# MineralFire-0_3-smd-inprogress.net
KiCad netlist of a schematic drawn in EAGLE
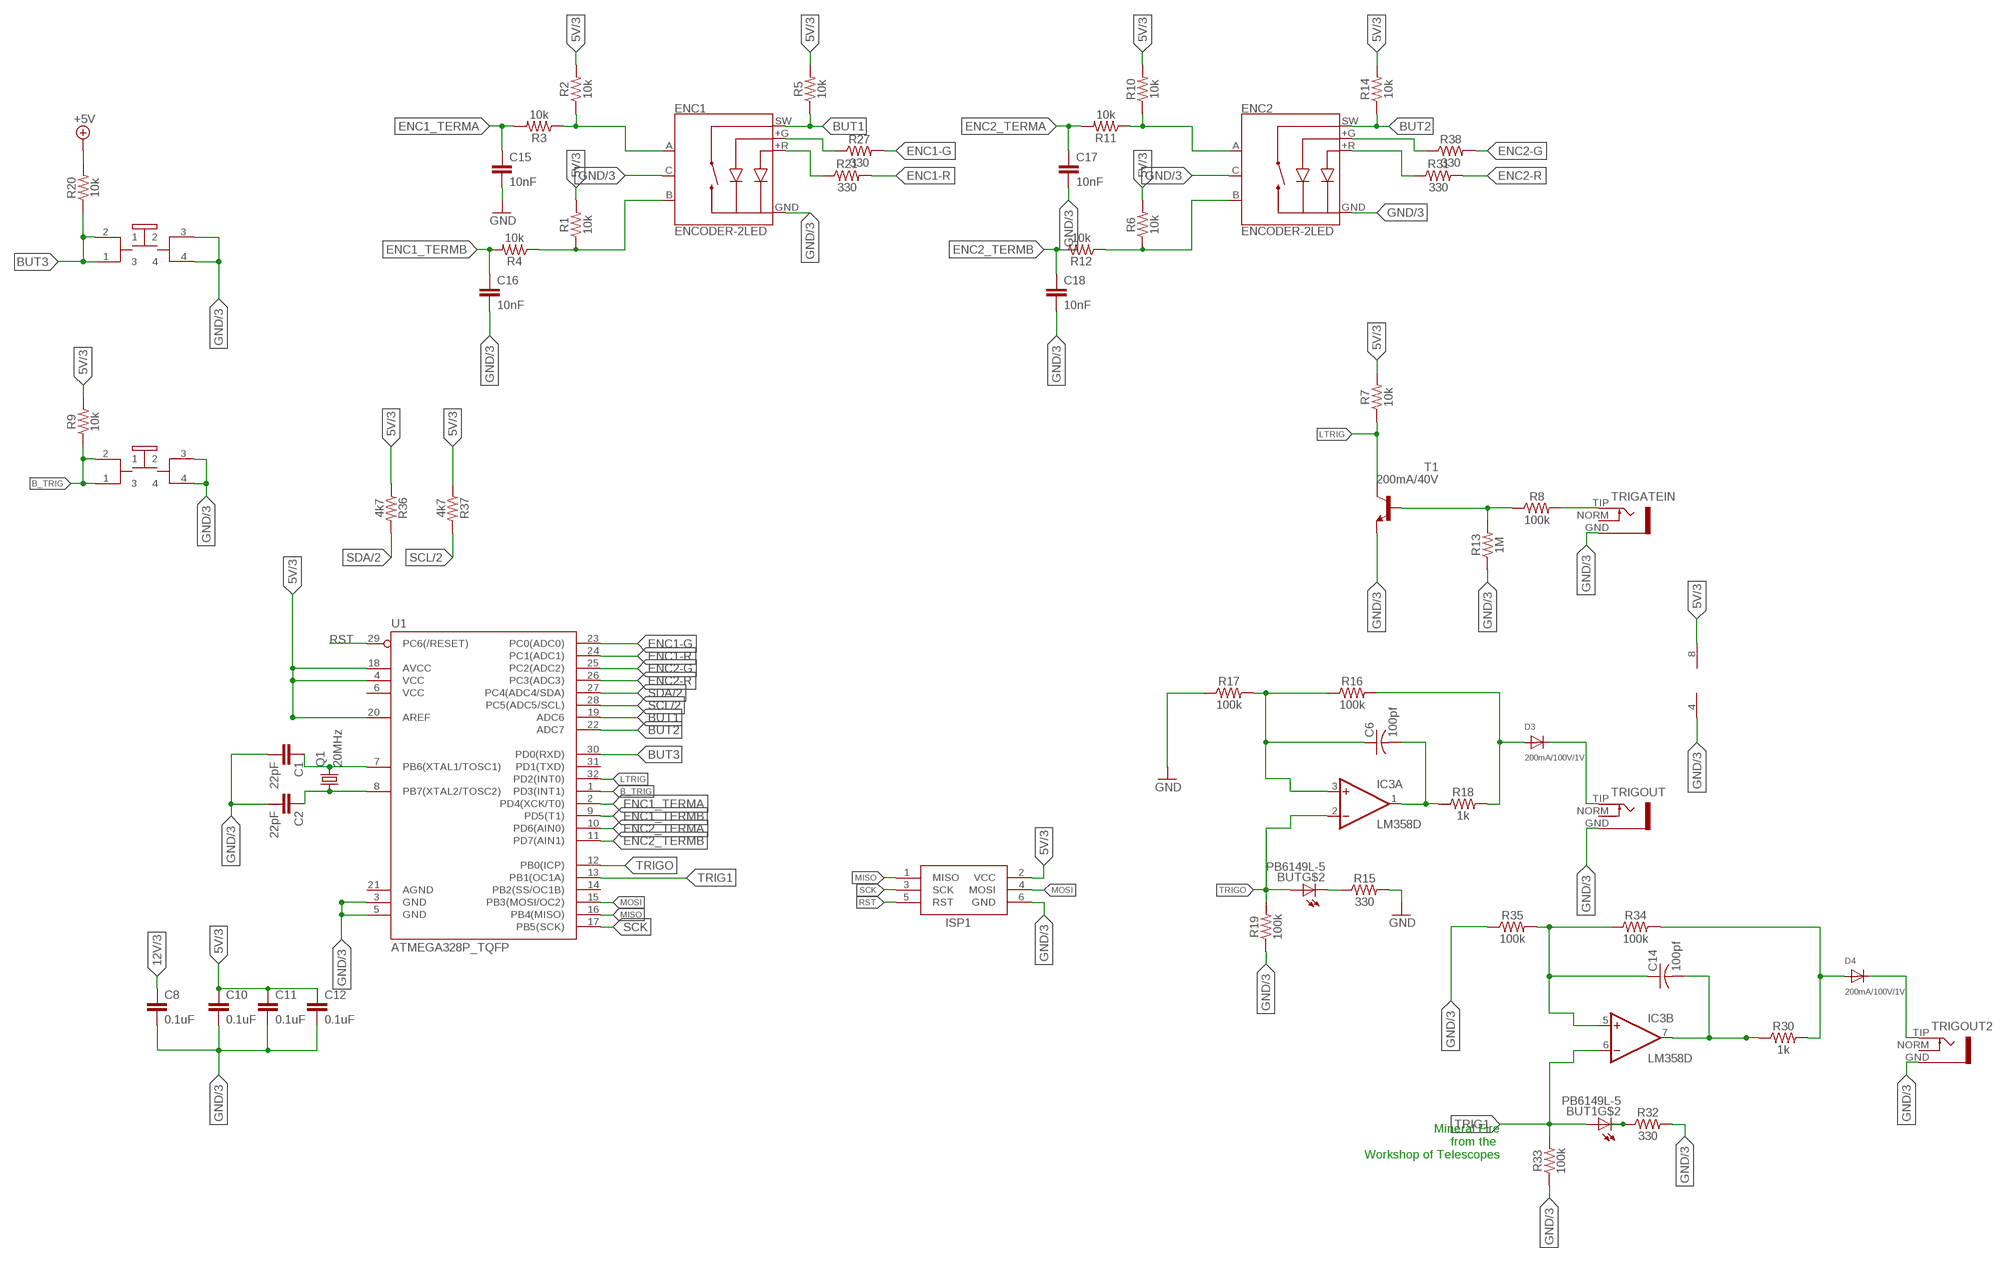
[diagram p0: schematic, sheet 1]
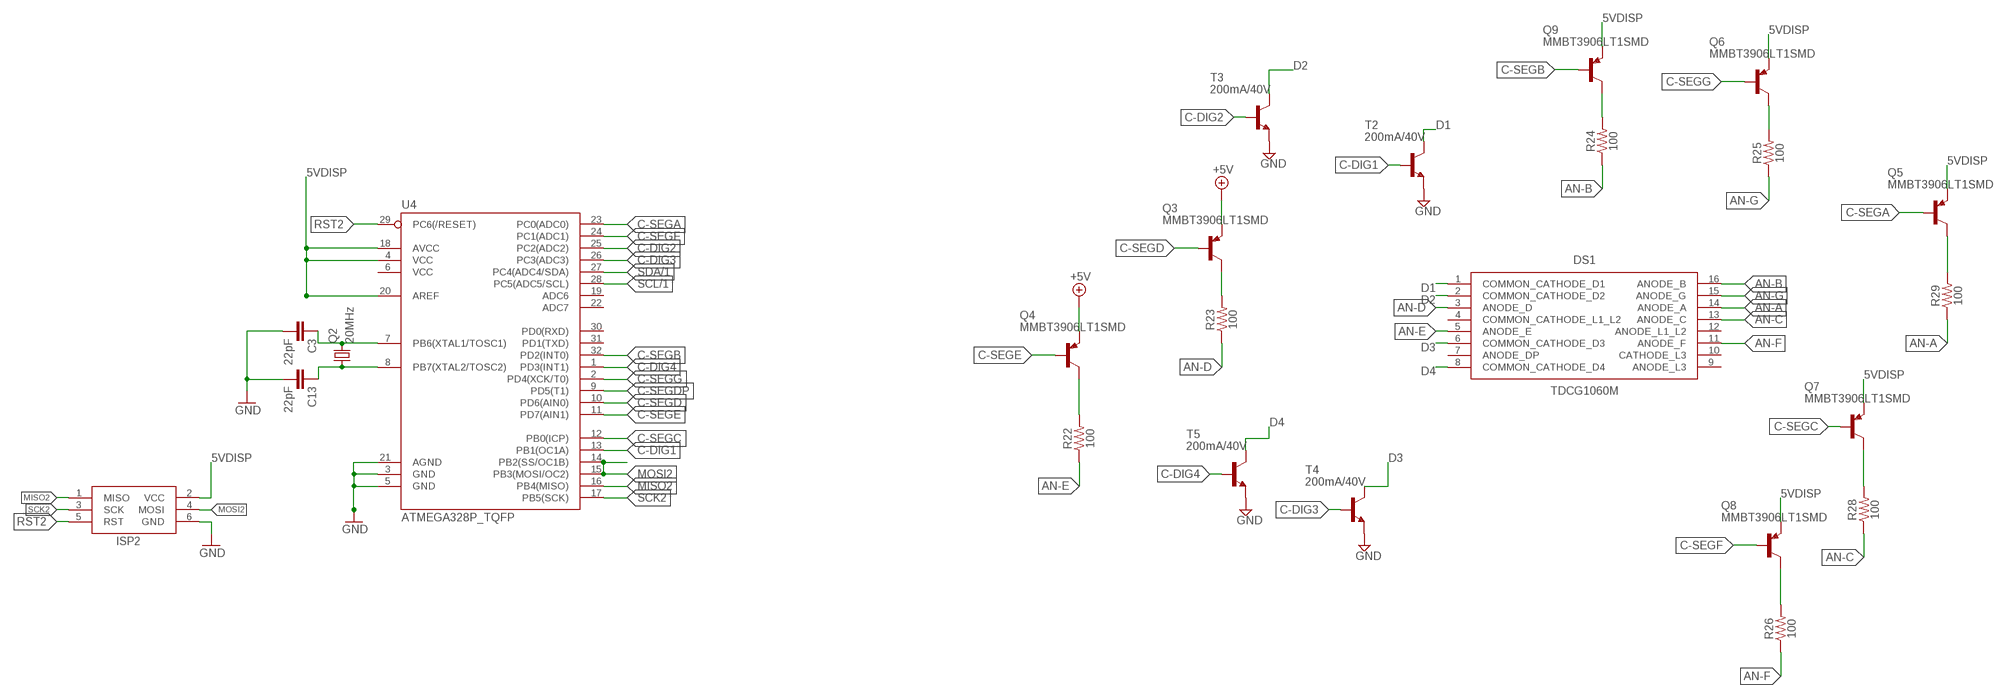
[diagram p1: schematic, sheet 2]
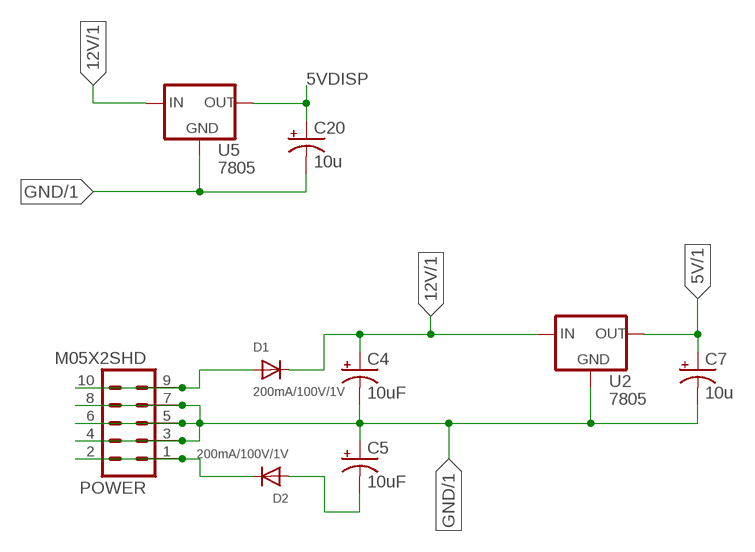
[diagram p2: schematic, sheet 3]

(export (version "E")
  (design (tool "Eeschema 10.0.6"))
  (components
    (comp (ref "C3")
      (value "22pF")
      (footprint "eagle-import:0603")
      (libsource (lib "eagle-import") (part "22PF-0603-50V-5%"))
    )
    (comp (ref "C13")
      (value "22pF")
      (footprint "eagle-import:0603")
      (libsource (lib "eagle-import") (part "22PF-0603-50V-5%"))
    )
    (comp (ref "DS1")
      (value "TDCG1060M")
      (footprint "eagle-import:DIPS1016W50P254L4020H700Q16N")
      (fields (field (name "RS_PART_NUMBER") "8187530P"))
      (libsource (lib "eagle-import") (part "TDCG1060M"))
    )
    (comp (ref "ISP2")
      (value "AVRISP-6")
      (footprint "eagle-import:AVRISP")
      (libsource (lib "eagle-import") (part "AVRISP-6"))
    )
    (comp (ref "Q2")
      (value "20MHz")
      (footprint "eagle-import:HC49UP")
      (libsource (lib "eagle-import") (part "CRYSTALHC49UP"))
    )
    (comp (ref "Q3")
      (value "MMBT3906LT1SMD")
      (footprint "eagle-import:SOT23-BEC")
      (libsource (lib "eagle-import") (part "MMBT3906SMDLT1"))
    )
    (comp (ref "Q4")
      (value "MMBT3906LT1SMD")
      (footprint "eagle-import:SOT23-BEC")
      (libsource (lib "eagle-import") (part "MMBT3906SMDLT1"))
    )
    (comp (ref "Q5")
      (value "MMBT3906LT1SMD")
      (footprint "eagle-import:SOT23-BEC")
      (libsource (lib "eagle-import") (part "MMBT3906SMDLT1"))
    )
    (comp (ref "Q6")
      (value "MMBT3906LT1SMD")
      (footprint "eagle-import:SOT23-BEC")
      (libsource (lib "eagle-import") (part "MMBT3906SMDLT1"))
    )
    (comp (ref "Q7")
      (value "MMBT3906LT1SMD")
      (footprint "eagle-import:SOT23-BEC")
      (libsource (lib "eagle-import") (part "MMBT3906SMDLT1"))
    )
    (comp (ref "Q8")
      (value "MMBT3906LT1SMD")
      (footprint "eagle-import:SOT23-BEC")
      (libsource (lib "eagle-import") (part "MMBT3906SMDLT1"))
    )
    (comp (ref "Q9")
      (value "MMBT3906LT1SMD")
      (footprint "eagle-import:SOT23-BEC")
      (libsource (lib "eagle-import") (part "MMBT3906SMDLT1"))
    )
    (comp (ref "R22")
      (value "100")
      (footprint "eagle-import:0603")
      (libsource (lib "eagle-import") (part "100OHM-0603-1/10W-1%"))
    )
    (comp (ref "R23")
      (value "100")
      (footprint "eagle-import:0603")
      (libsource (lib "eagle-import") (part "100OHM-0603-1/10W-1%"))
    )
    (comp (ref "R24")
      (value "100")
      (footprint "eagle-import:0603")
      (libsource (lib "eagle-import") (part "100OHM-0603-1/10W-1%"))
    )
    (comp (ref "R25")
      (value "100")
      (footprint "eagle-import:0603")
      (libsource (lib "eagle-import") (part "100OHM-0603-1/10W-1%"))
    )
    (comp (ref "R26")
      (value "100")
      (footprint "eagle-import:0603")
      (libsource (lib "eagle-import") (part "100OHM-0603-1/10W-1%"))
    )
    (comp (ref "R28")
      (value "100")
      (footprint "eagle-import:0603")
      (libsource (lib "eagle-import") (part "100OHM-0603-1/10W-1%"))
    )
    (comp (ref "R29")
      (value "100")
      (footprint "eagle-import:0603")
      (libsource (lib "eagle-import") (part "100OHM-0603-1/10W-1%"))
    )
    (comp (ref "T2")
      (value "200mA/40V")
      (footprint "eagle-import:SOT23-BEC")
      (libsource (lib "eagle-import") (part "-NPN-SOT23-BECMMBT3904LT1"))
    )
    (comp (ref "T3")
      (value "200mA/40V")
      (footprint "eagle-import:SOT23-BEC")
      (libsource (lib "eagle-import") (part "-NPN-SOT23-BECMMBT3904LT1"))
    )
    (comp (ref "T4")
      (value "200mA/40V")
      (footprint "eagle-import:SOT23-BEC")
      (libsource (lib "eagle-import") (part "-NPN-SOT23-BECMMBT3904LT1"))
    )
    (comp (ref "T5")
      (value "200mA/40V")
      (footprint "eagle-import:SOT23-BEC")
      (libsource (lib "eagle-import") (part "-NPN-SOT23-BECMMBT3904LT1"))
    )
    (comp (ref "U4")
      (value "ATMEGA328P_TQFP")
      (footprint "eagle-import:TQFP32-08")
      (libsource (lib "eagle-import") (part "ATMEGA328P_TQFP"))
    )
    (comp (ref "BUT")
      (value "PB6149L-5")
      (footprint "eagle-import:PB6149L")
      (libsource (lib "eagle-import") (part "PB6149L-5"))
    )
    (comp (ref "BUT1")
      (value "PB6149L-5")
      (footprint "eagle-import:PB6149L")
      (libsource (lib "eagle-import") (part "PB6149L-5"))
    )
    (comp (ref "C1")
      (value "22pF")
      (footprint "eagle-import:0603")
      (libsource (lib "eagle-import") (part "22PF-0603-50V-5%"))
    )
    (comp (ref "C2")
      (value "22pF")
      (footprint "eagle-import:0603")
      (libsource (lib "eagle-import") (part "22PF-0603-50V-5%"))
    )
    (comp (ref "C6")
      (value "100pf")
      (footprint "eagle-import:C0805K")
      (libsource (lib "eagle-import") (part "C-USC0805K"))
    )
    (comp (ref "C8")
      (value "0.1uF")
      (footprint "eagle-import:0603")
      (libsource (lib "eagle-import") (part "0.1UF-0603-100V-10%"))
    )
    (comp (ref "C10")
      (value "0.1uF")
      (footprint "eagle-import:0603")
      (libsource (lib "eagle-import") (part "0.1UF-0603-100V-10%"))
    )
    (comp (ref "C11")
      (value "0.1uF")
      (footprint "eagle-import:0603")
      (libsource (lib "eagle-import") (part "0.1UF-0603-100V-10%"))
    )
    (comp (ref "C12")
      (value "0.1uF")
      (footprint "eagle-import:0603")
      (libsource (lib "eagle-import") (part "0.1UF-0603-100V-10%"))
    )
    (comp (ref "C14")
      (value "100pf")
      (footprint "eagle-import:C0805K")
      (libsource (lib "eagle-import") (part "C-USC0805K"))
    )
    (comp (ref "C15")
      (value "10nF")
      (footprint "eagle-import:0603")
      (libsource (lib "eagle-import") (part "10NF-0603-50V-10%"))
    )
    (comp (ref "C16")
      (value "10nF")
      (footprint "eagle-import:0603")
      (libsource (lib "eagle-import") (part "10NF-0603-50V-10%"))
    )
    (comp (ref "C17")
      (value "10nF")
      (footprint "eagle-import:0603")
      (libsource (lib "eagle-import") (part "10NF-0603-50V-10%"))
    )
    (comp (ref "C18")
      (value "10nF")
      (footprint "eagle-import:0603")
      (libsource (lib "eagle-import") (part "10NF-0603-50V-10%"))
    )
    (comp (ref "D3")
      (value "200mA/100V/1V")
      (footprint "eagle-import:SMADIODE")
      (libsource (lib "eagle-import") (part "DIODESMA"))
    )
    (comp (ref "D4")
      (value "200mA/100V/1V")
      (footprint "eagle-import:SMADIODE")
      (libsource (lib "eagle-import") (part "DIODESMA"))
    )
    (comp (ref "ENC1")
      (value "ENCODER-2LED")
      (footprint "eagle-import:ENCODER_LED_2")
      (libsource (lib "eagle-import") (part "ENCODER-2LED"))
    )
    (comp (ref "ENC2")
      (value "ENCODER-2LED")
      (footprint "eagle-import:ENCODER_LED_2")
      (libsource (lib "eagle-import") (part "ENCODER-2LED"))
    )
    (comp (ref "IC3")
      (value "LM358D")
      (footprint "eagle-import:SO08")
      (libsource (lib "eagle-import") (part "LM358D"))
    )
    (comp (ref "ISP1")
      (value "AVRISP-6")
      (footprint "eagle-import:AVRISP")
      (libsource (lib "eagle-import") (part "AVRISP-6"))
    )
    (comp (ref "Q1")
      (value "20MHz")
      (footprint "eagle-import:HC49UP")
      (libsource (lib "eagle-import") (part "CRYSTALHC49UP"))
    )
    (comp (ref "R1")
      (value "10k")
      (footprint "eagle-import:0603")
      (libsource (lib "eagle-import") (part "10KOHM-0603-1/10W-1%"))
    )
    (comp (ref "R2")
      (value "10k")
      (footprint "eagle-import:0603")
      (libsource (lib "eagle-import") (part "10KOHM-0603-1/10W-1%"))
    )
    (comp (ref "R3")
      (value "10k")
      (footprint "eagle-import:0603")
      (libsource (lib "eagle-import") (part "10KOHM-0603-1/10W-1%"))
    )
    (comp (ref "R4")
      (value "10k")
      (footprint "eagle-import:0603")
      (libsource (lib "eagle-import") (part "10KOHM-0603-1/10W-1%"))
    )
    (comp (ref "R5")
      (value "10k")
      (footprint "eagle-import:0603")
      (libsource (lib "eagle-import") (part "10KOHM-0603-1/10W-1%"))
    )
    (comp (ref "R6")
      (value "10k")
      (footprint "eagle-import:0603")
      (libsource (lib "eagle-import") (part "10KOHM-0603-1/10W-1%"))
    )
    (comp (ref "R7")
      (value "10k")
      (footprint "eagle-import:0603")
      (libsource (lib "eagle-import") (part "10KOHM-0603-1/10W-1%"))
    )
    (comp (ref "R8")
      (value "100k")
      (footprint "eagle-import:0603")
      (libsource (lib "eagle-import") (part "100KOHM-0603-1/10W-1%"))
    )
    (comp (ref "R9")
      (value "10k")
      (footprint "eagle-import:0603")
      (libsource (lib "eagle-import") (part "10KOHM-0603-1/10W-1%"))
    )
    (comp (ref "R10")
      (value "10k")
      (footprint "eagle-import:0603")
      (libsource (lib "eagle-import") (part "10KOHM-0603-1/10W-1%"))
    )
    (comp (ref "R11")
      (value "10k")
      (footprint "eagle-import:0603")
      (libsource (lib "eagle-import") (part "10KOHM-0603-1/10W-1%"))
    )
    (comp (ref "R12")
      (value "10k")
      (footprint "eagle-import:0603")
      (libsource (lib "eagle-import") (part "10KOHM-0603-1/10W-1%"))
    )
    (comp (ref "R13")
      (value "1M")
      (footprint "eagle-import:0603")
      (libsource (lib "eagle-import") (part "1MOHM-0603-1/4W-5%"))
    )
    (comp (ref "R14")
      (value "10k")
      (footprint "eagle-import:0603")
      (libsource (lib "eagle-import") (part "10KOHM-0603-1/10W-1%"))
    )
    (comp (ref "R15")
      (value "330")
      (footprint "eagle-import:0603")
      (libsource (lib "eagle-import") (part "330OHM-0603-1/10W-1%"))
    )
    (comp (ref "R16")
      (value "100k")
      (footprint "eagle-import:0603")
      (libsource (lib "eagle-import") (part "100KOHM-0603-1/10W-1%"))
    )
    (comp (ref "R17")
      (value "100k")
      (footprint "eagle-import:0603")
      (libsource (lib "eagle-import") (part "100KOHM-0603-1/10W-1%"))
    )
    (comp (ref "R18")
      (value "1k")
      (footprint "eagle-import:0603")
      (libsource (lib "eagle-import") (part "1KOHM-0603-1/10W-1%"))
    )
    (comp (ref "R19")
      (value "100k")
      (footprint "eagle-import:0603")
      (libsource (lib "eagle-import") (part "100KOHM-0603-1/10W-1%"))
    )
    (comp (ref "R20")
      (value "10k")
      (footprint "eagle-import:0603")
      (libsource (lib "eagle-import") (part "10KOHM-0603-1/10W-1%"))
    )
    (comp (ref "R21")
      (value "330")
      (footprint "eagle-import:0603")
      (libsource (lib "eagle-import") (part "330OHM-0603-1/10W-1%"))
    )
    (comp (ref "R27")
      (value "330")
      (footprint "eagle-import:0603")
      (libsource (lib "eagle-import") (part "330OHM-0603-1/10W-1%"))
    )
    (comp (ref "R30")
      (value "1k")
      (footprint "eagle-import:0603")
      (libsource (lib "eagle-import") (part "1KOHM-0603-1/10W-1%"))
    )
    (comp (ref "R31")
      (value "330")
      (footprint "eagle-import:0603")
      (libsource (lib "eagle-import") (part "330OHM-0603-1/10W-1%"))
    )
    (comp (ref "R32")
      (value "330")
      (footprint "eagle-import:0603")
      (libsource (lib "eagle-import") (part "330OHM-0603-1/10W-1%"))
    )
    (comp (ref "R33")
      (value "100k")
      (footprint "eagle-import:0603")
      (libsource (lib "eagle-import") (part "100KOHM-0603-1/10W-1%"))
    )
    (comp (ref "R34")
      (value "100k")
      (footprint "eagle-import:0603")
      (libsource (lib "eagle-import") (part "100KOHM-0603-1/10W-1%"))
    )
    (comp (ref "R35")
      (value "100k")
      (footprint "eagle-import:0603")
      (libsource (lib "eagle-import") (part "100KOHM-0603-1/10W-1%"))
    )
    (comp (ref "R36")
      (value "4k7")
      (footprint "eagle-import:0603")
      (libsource (lib "eagle-import") (part "1KOHM-0603-1/10W-1%"))
    )
    (comp (ref "R37")
      (value "4k7")
      (footprint "eagle-import:0603")
      (libsource (lib "eagle-import") (part "1KOHM-0603-1/10W-1%"))
    )
    (comp (ref "R38")
      (value "330")
      (footprint "eagle-import:0603")
      (libsource (lib "eagle-import") (part "330OHM-0603-1/10W-1%"))
    )
    (comp (ref "T1")
      (value "200mA/40V")
      (footprint "eagle-import:SOT23-BEC")
      (libsource (lib "eagle-import") (part "-NPN-SOT23-BECMMBT3904LT1"))
    )
    (comp (ref "TRIGATEIN")
      (value "S_JACK")
      (footprint "eagle-import:S_JACK")
      (libsource (lib "eagle-import") (part "S_JACK"))
    )
    (comp (ref "TRIGOUT")
      (value "S_JACK")
      (footprint "eagle-import:S_JACK")
      (libsource (lib "eagle-import") (part "S_JACK"))
    )
    (comp (ref "TRIGOUT2")
      (value "S_JACK")
      (footprint "eagle-import:S_JACK")
      (libsource (lib "eagle-import") (part "S_JACK"))
    )
    (comp (ref "U1")
      (value "ATMEGA328P_TQFP")
      (footprint "eagle-import:TQFP32-08")
      (libsource (lib "eagle-import") (part "ATMEGA328P_TQFP"))
    )
    (comp (ref "C4")
      (value "10uF")
      (footprint "eagle-import:153CLV-0505")
      (libsource (lib "eagle-import") (part "rcl_334_CPOL-US153CLV-0505"))
    )
    (comp (ref "C5")
      (value "10uF")
      (footprint "eagle-import:153CLV-0505")
      (libsource (lib "eagle-import") (part "rcl_334_CPOL-US153CLV-0505"))
    )
    (comp (ref "C7")
      (value "10u")
      (footprint "eagle-import:153CLV-0505")
      (libsource (lib "eagle-import") (part "CPOL-US153CLV-0505"))
    )
    (comp (ref "C20")
      (value "10u")
      (footprint "eagle-import:153CLV-0505")
      (libsource (lib "eagle-import") (part "CPOL-US153CLV-0505"))
    )
    (comp (ref "D1")
      (value "200mA/100V/1V")
      (footprint "eagle-import:SMADIODE")
      (libsource (lib "eagle-import") (part "DIODESMA"))
    )
    (comp (ref "D2")
      (value "200mA/100V/1V")
      (footprint "eagle-import:SMADIODE")
      (libsource (lib "eagle-import") (part "DIODESMA"))
    )
    (comp (ref "POWER")
      (value "M05X2SHD")
      (footprint "eagle-import:2X5-SHROUDED")
      (libsource (lib "eagle-import") (part "M05X2SHD"))
    )
    (comp (ref "U2")
      (value "7805")
      (footprint "eagle-import:V-REG")
      (libsource (lib "eagle-import") (part "V-REG"))
    )
    (comp (ref "U5")
      (value "7805")
      (footprint "eagle-import:V-REG")
      (libsource (lib "eagle-import") (part "V-REG"))
    )
  )
  (nets
    (net (code "1") (name "+5V") (class "Default")
      (node (ref "Q3") (pin "E") (pinfunction "E_E") (pintype "passive"))
      (node (ref "Q4") (pin "E") (pinfunction "E_E") (pintype "passive"))
      (node (ref "R20") (pin "2") (pinfunction "2_2") (pintype "passive"))
    )
    (net (code "2") (name "5V") (class "Default")
      (node (ref "C10") (pin "1") (pinfunction "1_1") (pintype "passive"))
      (node (ref "C11") (pin "1") (pinfunction "1_1") (pintype "passive"))
      (node (ref "C12") (pin "1") (pinfunction "1_1") (pintype "passive"))
      (node (ref "C7") (pin "+") (pinfunction "+_+") (pintype "passive"))
      (node (ref "IC3") (pin "8") (pinfunction "V+_8") (pintype "power_in"))
      (node (ref "ISP1") (pin "2") (pinfunction "VCC_2") (pintype "power_in"))
      (node (ref "R1") (pin "2") (pinfunction "2_2") (pintype "passive"))
      (node (ref "R10") (pin "2") (pinfunction "2_2") (pintype "passive"))
      (node (ref "R14") (pin "2") (pinfunction "2_2") (pintype "passive"))
      (node (ref "R2") (pin "2") (pinfunction "2_2") (pintype "passive"))
      (node (ref "R36") (pin "1") (pinfunction "1_1") (pintype "passive"))
      (node (ref "R37") (pin "1") (pinfunction "1_1") (pintype "passive"))
      (node (ref "R5") (pin "2") (pinfunction "2_2") (pintype "passive"))
      (node (ref "R6") (pin "2") (pinfunction "2_2") (pintype "passive"))
      (node (ref "R7") (pin "2") (pinfunction "2_2") (pintype "passive"))
      (node (ref "R9") (pin "2") (pinfunction "2_2") (pintype "passive"))
      (node (ref "U1") (pin "18") (pinfunction "AVCC_18") (pintype "bidirectional"))
      (node (ref "U1") (pin "20") (pinfunction "AREF_20") (pintype "bidirectional"))
      (node (ref "U1") (pin "4") (pinfunction "VCC_4") (pintype "bidirectional"))
      (node (ref "U2") (pin "3") (pinfunction "OUT_3") (pintype "passive"))
    )
    (net (code "3") (name "5VDISP") (class "Default")
      (node (ref "C20") (pin "+") (pinfunction "+_+") (pintype "passive"))
      (node (ref "ISP2") (pin "2") (pinfunction "VCC_2") (pintype "power_in"))
      (node (ref "Q5") (pin "E") (pinfunction "E_E") (pintype "passive"))
      (node (ref "Q6") (pin "E") (pinfunction "E_E") (pintype "passive"))
      (node (ref "Q7") (pin "E") (pinfunction "E_E") (pintype "passive"))
      (node (ref "Q8") (pin "E") (pinfunction "E_E") (pintype "passive"))
      (node (ref "Q9") (pin "E") (pinfunction "E_E") (pintype "passive"))
      (node (ref "U4") (pin "18") (pinfunction "AVCC_18") (pintype "bidirectional"))
      (node (ref "U4") (pin "20") (pinfunction "AREF_20") (pintype "bidirectional"))
      (node (ref "U4") (pin "4") (pinfunction "VCC_4") (pintype "bidirectional"))
      (node (ref "U5") (pin "3") (pinfunction "OUT_3") (pintype "passive"))
    )
    (net (code "4") (name "12V") (class "Default")
      (node (ref "C4") (pin "+") (pinfunction "+_+") (pintype "passive"))
      (node (ref "C8") (pin "1") (pinfunction "1_1") (pintype "passive"))
      (node (ref "D1") (pin "C") (pinfunction "C_C") (pintype "passive"))
      (node (ref "U2") (pin "1") (pinfunction "IN_1") (pintype "input"))
      (node (ref "U5") (pin "1") (pinfunction "IN_1") (pintype "input"))
    )
    (net (code "5") (name "AN-A") (class "Default")
      (node (ref "DS1") (pin "14") (pinfunction "ANODE_A_14") (pintype "input"))
      (node (ref "R29") (pin "1") (pinfunction "1_1") (pintype "passive"))
    )
    (net (code "6") (name "AN-B") (class "Default")
      (node (ref "DS1") (pin "16") (pinfunction "ANODE_B_16") (pintype "input"))
      (node (ref "R24") (pin "1") (pinfunction "1_1") (pintype "passive"))
    )
    (net (code "7") (name "AN-C") (class "Default")
      (node (ref "DS1") (pin "13") (pinfunction "ANODE_C_13") (pintype "input"))
      (node (ref "R28") (pin "1") (pinfunction "1_1") (pintype "passive"))
    )
    (net (code "8") (name "AN-D") (class "Default")
      (node (ref "DS1") (pin "3") (pinfunction "ANODE_D_3") (pintype "input"))
      (node (ref "R23") (pin "1") (pinfunction "1_1") (pintype "passive"))
    )
    (net (code "9") (name "AN-E") (class "Default")
      (node (ref "DS1") (pin "5") (pinfunction "ANODE_E_5") (pintype "input"))
      (node (ref "R22") (pin "1") (pinfunction "1_1") (pintype "passive"))
    )
    (net (code "10") (name "AN-F") (class "Default")
      (node (ref "DS1") (pin "11") (pinfunction "ANODE_F_11") (pintype "input"))
      (node (ref "R26") (pin "1") (pinfunction "1_1") (pintype "passive"))
    )
    (net (code "11") (name "AN-G") (class "Default")
      (node (ref "DS1") (pin "15") (pinfunction "ANODE_G_15") (pintype "input"))
      (node (ref "R25") (pin "1") (pinfunction "1_1") (pintype "passive"))
    )
    (net (code "12") (name "BUT1") (class "Default")
      (node (ref "ENC1") (pin "SW") (pinfunction "SW_SW") (pintype "passive"))
      (node (ref "R5") (pin "1") (pinfunction "1_1") (pintype "passive"))
      (node (ref "U1") (pin "19") (pinfunction "ADC6_19") (pintype "bidirectional"))
    )
    (net (code "13") (name "BUT2") (class "Default")
      (node (ref "ENC2") (pin "SW") (pinfunction "SW_SW") (pintype "passive"))
      (node (ref "R14") (pin "1") (pinfunction "1_1") (pintype "passive"))
      (node (ref "U1") (pin "22") (pinfunction "ADC7_22") (pintype "bidirectional"))
    )
    (net (code "14") (name "BUT3") (class "Default")
      (node (ref "BUT1") (pin "1") (pinfunction "3_1") (pintype "bidirectional"))
      (node (ref "BUT1") (pin "2") (pinfunction "1_2") (pintype "bidirectional"))
      (node (ref "R20") (pin "1") (pinfunction "1_1") (pintype "passive"))
      (node (ref "U1") (pin "30") (pinfunction "PD0(RXD)_30") (pintype "bidirectional"))
    )
    (net (code "15") (name "B_TRIG") (class "Default")
      (node (ref "BUT") (pin "1") (pinfunction "3_1") (pintype "bidirectional"))
      (node (ref "BUT") (pin "2") (pinfunction "1_2") (pintype "bidirectional"))
      (node (ref "R9") (pin "1") (pinfunction "1_1") (pintype "passive"))
      (node (ref "U1") (pin "1") (pinfunction "PD3(INT1)_1") (pintype "bidirectional"))
    )
    (net (code "16") (name "C-DIG1") (class "Default")
      (node (ref "T2") (pin "B") (pinfunction "B_B") (pintype "passive"))
      (node (ref "U4") (pin "13") (pinfunction "PB1(OC1A)_13") (pintype "bidirectional"))
    )
    (net (code "17") (name "C-DIG2") (class "Default")
      (node (ref "T3") (pin "B") (pinfunction "B_B") (pintype "passive"))
      (node (ref "U4") (pin "25") (pinfunction "PC2(ADC2)_25") (pintype "bidirectional"))
    )
    (net (code "18") (name "C-DIG3") (class "Default")
      (node (ref "T4") (pin "B") (pinfunction "B_B") (pintype "passive"))
      (node (ref "U4") (pin "26") (pinfunction "PC3(ADC3)_26") (pintype "bidirectional"))
    )
    (net (code "19") (name "C-DIG4") (class "Default")
      (node (ref "T5") (pin "B") (pinfunction "B_B") (pintype "passive"))
      (node (ref "U4") (pin "1") (pinfunction "PD3(INT1)_1") (pintype "bidirectional"))
    )
    (net (code "20") (name "C-SEGA") (class "Default")
      (node (ref "Q5") (pin "B") (pinfunction "B_B") (pintype "passive"))
      (node (ref "U4") (pin "23") (pinfunction "PC0(ADC0)_23") (pintype "bidirectional"))
    )
    (net (code "21") (name "C-SEGB") (class "Default")
      (node (ref "Q9") (pin "B") (pinfunction "B_B") (pintype "passive"))
      (node (ref "U4") (pin "32") (pinfunction "PD2(INT0)_32") (pintype "bidirectional"))
    )
    (net (code "22") (name "C-SEGC") (class "Default")
      (node (ref "Q7") (pin "B") (pinfunction "B_B") (pintype "passive"))
      (node (ref "U4") (pin "12") (pinfunction "PB0(ICP)_12") (pintype "bidirectional"))
    )
    (net (code "23") (name "C-SEGD") (class "Default")
      (node (ref "Q3") (pin "B") (pinfunction "B_B") (pintype "passive"))
      (node (ref "U4") (pin "10") (pinfunction "PD6(AIN0)_10") (pintype "bidirectional"))
    )
    (net (code "24") (name "C-SEGDP") (class "Default")
      (node (ref "U4") (pin "9") (pinfunction "PD5(T1)_9") (pintype "bidirectional"))
    )
    (net (code "25") (name "C-SEGE") (class "Default")
      (node (ref "Q4") (pin "B") (pinfunction "B_B") (pintype "passive"))
      (node (ref "U4") (pin "11") (pinfunction "PD7(AIN1)_11") (pintype "bidirectional"))
    )
    (net (code "26") (name "C-SEGF") (class "Default")
      (node (ref "Q8") (pin "B") (pinfunction "B_B") (pintype "passive"))
      (node (ref "U4") (pin "24") (pinfunction "PC1(ADC1)_24") (pintype "bidirectional"))
    )
    (net (code "27") (name "C-SEGG") (class "Default")
      (node (ref "Q6") (pin "B") (pinfunction "B_B") (pintype "passive"))
      (node (ref "U4") (pin "2") (pinfunction "PD4(XCK/T0)_2") (pintype "bidirectional"))
    )
    (net (code "28") (name "D1") (class "Default")
      (node (ref "DS1") (pin "1") (pinfunction "COMMON_CATHODE_D1_1") (pintype "input"))
      (node (ref "T2") (pin "C") (pinfunction "C_C") (pintype "passive"))
    )
    (net (code "29") (name "D2") (class "Default")
      (node (ref "DS1") (pin "2") (pinfunction "COMMON_CATHODE_D2_2") (pintype "input"))
      (node (ref "T3") (pin "C") (pinfunction "C_C") (pintype "passive"))
    )
    (net (code "30") (name "D3") (class "Default")
      (node (ref "DS1") (pin "6") (pinfunction "COMMON_CATHODE_D3_6") (pintype "input"))
      (node (ref "T4") (pin "C") (pinfunction "C_C") (pintype "passive"))
    )
    (net (code "31") (name "D4") (class "Default")
      (node (ref "DS1") (pin "8") (pinfunction "COMMON_CATHODE_D4_8") (pintype "input"))
      (node (ref "T5") (pin "C") (pinfunction "C_C") (pintype "passive"))
    )
    (net (code "32") (name "ENC1-G") (class "Default")
      (node (ref "R27") (pin "2") (pinfunction "2_2") (pintype "passive"))
      (node (ref "U1") (pin "23") (pinfunction "PC0(ADC0)_23") (pintype "bidirectional"))
    )
    (net (code "33") (name "ENC1-R") (class "Default")
      (node (ref "R21") (pin "2") (pinfunction "2_2") (pintype "passive"))
      (node (ref "U1") (pin "24") (pinfunction "PC1(ADC1)_24") (pintype "bidirectional"))
    )
    (net (code "34") (name "ENC1_TERMA") (class "Default")
      (node (ref "C15") (pin "1") (pinfunction "1_1") (pintype "passive"))
      (node (ref "R3") (pin "2") (pinfunction "2_2") (pintype "passive"))
      (node (ref "U1") (pin "2") (pinfunction "PD4(XCK/T0)_2") (pintype "bidirectional"))
    )
    (net (code "35") (name "ENC1_TERMB") (class "Default")
      (node (ref "C16") (pin "1") (pinfunction "1_1") (pintype "passive"))
      (node (ref "R4") (pin "2") (pinfunction "2_2") (pintype "passive"))
      (node (ref "U1") (pin "9") (pinfunction "PD5(T1)_9") (pintype "bidirectional"))
    )
    (net (code "36") (name "ENC2-G") (class "Default")
      (node (ref "R38") (pin "2") (pinfunction "2_2") (pintype "passive"))
      (node (ref "U1") (pin "25") (pinfunction "PC2(ADC2)_25") (pintype "bidirectional"))
    )
    (net (code "37") (name "ENC2-R") (class "Default")
      (node (ref "R31") (pin "2") (pinfunction "2_2") (pintype "passive"))
      (node (ref "U1") (pin "26") (pinfunction "PC3(ADC3)_26") (pintype "bidirectional"))
    )
    (net (code "38") (name "ENC2_TERMA") (class "Default")
      (node (ref "C17") (pin "1") (pinfunction "1_1") (pintype "passive"))
      (node (ref "R11") (pin "2") (pinfunction "2_2") (pintype "passive"))
      (node (ref "U1") (pin "10") (pinfunction "PD6(AIN0)_10") (pintype "bidirectional"))
    )
    (net (code "39") (name "ENC2_TERMB") (class "Default")
      (node (ref "C18") (pin "1") (pinfunction "1_1") (pintype "passive"))
      (node (ref "R12") (pin "2") (pinfunction "2_2") (pintype "passive"))
      (node (ref "U1") (pin "11") (pinfunction "PD7(AIN1)_11") (pintype "bidirectional"))
    )
    (net (code "40") (name "GND") (class "Default")
      (node (ref "BUT") (pin "3") (pinfunction "2_3") (pintype "bidirectional"))
      (node (ref "BUT") (pin "4") (pinfunction "4_4") (pintype "bidirectional"))
      (node (ref "BUT1") (pin "3") (pinfunction "2_3") (pintype "bidirectional"))
      (node (ref "BUT1") (pin "4") (pinfunction "4_4") (pintype "bidirectional"))
      (node (ref "C1") (pin "2") (pinfunction "2_2") (pintype "passive"))
      (node (ref "C10") (pin "2") (pinfunction "2_2") (pintype "passive"))
      (node (ref "C11") (pin "2") (pinfunction "2_2") (pintype "passive"))
      (node (ref "C12") (pin "2") (pinfunction "2_2") (pintype "passive"))
      (node (ref "C13") (pin "2") (pinfunction "2_2") (pintype "passive"))
      (node (ref "C15") (pin "2") (pinfunction "2_2") (pintype "passive"))
      (node (ref "C16") (pin "2") (pinfunction "2_2") (pintype "passive"))
      (node (ref "C17") (pin "2") (pinfunction "2_2") (pintype "passive"))
      (node (ref "C18") (pin "2") (pinfunction "2_2") (pintype "passive"))
      (node (ref "C2") (pin "2") (pinfunction "2_2") (pintype "passive"))
      (node (ref "C20") (pin "-") (pinfunction "-_-") (pintype "passive"))
      (node (ref "C3") (pin "2") (pinfunction "2_2") (pintype "passive"))
      (node (ref "C4") (pin "-") (pinfunction "-_-") (pintype "passive"))
      (node (ref "C5") (pin "+") (pinfunction "+_+") (pintype "passive"))
      (node (ref "C7") (pin "-") (pinfunction "-_-") (pintype "passive"))
      (node (ref "C8") (pin "2") (pinfunction "2_2") (pintype "passive"))
      (node (ref "ENC1") (pin "C") (pinfunction "C_C") (pintype "bidirectional"))
      (node (ref "ENC1") (pin "GND") (pinfunction "-_GND") (pintype "passive"))
      (node (ref "ENC2") (pin "C") (pinfunction "C_C") (pintype "bidirectional"))
      (node (ref "ENC2") (pin "GND") (pinfunction "-_GND") (pintype "passive"))
      (node (ref "IC3") (pin "4") (pinfunction "V-_4") (pintype "power_in"))
      (node (ref "ISP1") (pin "6") (pinfunction "GND_6") (pintype "power_in"))
      (node (ref "ISP2") (pin "6") (pinfunction "GND_6") (pintype "power_in"))
      (node (ref "POWER") (pin "3") (pinfunction "3_3") (pintype "passive"))
      (node (ref "POWER") (pin "4") (pinfunction "4_4") (pintype "passive"))
      (node (ref "POWER") (pin "5") (pinfunction "5_5") (pintype "passive"))
      (node (ref "POWER") (pin "6") (pinfunction "6_6") (pintype "passive"))
      (node (ref "POWER") (pin "7") (pinfunction "7_7") (pintype "passive"))
      (node (ref "POWER") (pin "8") (pinfunction "8_8") (pintype "passive"))
      (node (ref "R13") (pin "1") (pinfunction "1_1") (pintype "passive"))
      (node (ref "R15") (pin "2") (pinfunction "2_2") (pintype "passive"))
      (node (ref "R17") (pin "1") (pinfunction "1_1") (pintype "passive"))
      (node (ref "R19") (pin "1") (pinfunction "1_1") (pintype "passive"))
      (node (ref "R32") (pin "2") (pinfunction "2_2") (pintype "passive"))
      (node (ref "R33") (pin "1") (pinfunction "1_1") (pintype "passive"))
      (node (ref "R35") (pin "1") (pinfunction "1_1") (pintype "passive"))
      (node (ref "T1") (pin "E") (pinfunction "E_E") (pintype "passive"))
      (node (ref "T2") (pin "E") (pinfunction "E_E") (pintype "passive"))
      (node (ref "T3") (pin "E") (pinfunction "E_E") (pintype "passive"))
      (node (ref "T4") (pin "E") (pinfunction "E_E") (pintype "passive"))
      (node (ref "T5") (pin "E") (pinfunction "E_E") (pintype "passive"))
      (node (ref "TRIGATEIN") (pin "GND") (pinfunction "GND_GND") (pintype "passive"))
      (node (ref "TRIGOUT") (pin "GND") (pinfunction "GND_GND") (pintype "passive"))
      (node (ref "TRIGOUT2") (pin "GND") (pinfunction "GND_GND") (pintype "passive"))
      (node (ref "U1") (pin "3") (pinfunction "GND_3") (pintype "bidirectional"))
      (node (ref "U1") (pin "5") (pinfunction "GND_5") (pintype "bidirectional"))
      (node (ref "U2") (pin "4") (pinfunction "GND_4") (pintype "input"))
      (node (ref "U4") (pin "21") (pinfunction "AGND_21") (pintype "bidirectional"))
      (node (ref "U4") (pin "3") (pinfunction "GND_3") (pintype "bidirectional"))
      (node (ref "U4") (pin "5") (pinfunction "GND_5") (pintype "bidirectional"))
      (node (ref "U5") (pin "4") (pinfunction "GND_4") (pintype "input"))
    )
    (net (code "41") (name "LTRIG") (class "Default")
      (node (ref "R7") (pin "1") (pinfunction "1_1") (pintype "passive"))
      (node (ref "T1") (pin "C") (pinfunction "C_C") (pintype "passive"))
      (node (ref "U1") (pin "32") (pinfunction "PD2(INT0)_32") (pintype "bidirectional"))
    )
    (net (code "42") (name "MISO") (class "Default")
      (node (ref "ISP1") (pin "1") (pinfunction "MISO_1") (pintype "input"))
      (node (ref "U1") (pin "16") (pinfunction "PB4(MISO)_16") (pintype "bidirectional"))
    )
    (net (code "43") (name "MISO2") (class "Default")
      (node (ref "ISP2") (pin "1") (pinfunction "MISO_1") (pintype "input"))
      (node (ref "U4") (pin "16") (pinfunction "PB4(MISO)_16") (pintype "bidirectional"))
    )
    (net (code "44") (name "MOSI") (class "Default")
      (node (ref "ISP1") (pin "4") (pinfunction "MOSI_4") (pintype "output"))
      (node (ref "U1") (pin "15") (pinfunction "PB3(MOSI/OC2)_15") (pintype "bidirectional"))
    )
    (net (code "45") (name "MOSI2") (class "Default")
      (node (ref "ISP2") (pin "4") (pinfunction "MOSI_4") (pintype "output"))
      (node (ref "U4") (pin "14") (pinfunction "PB2(SS/OC1B)_14") (pintype "bidirectional"))
      (node (ref "U4") (pin "15") (pinfunction "PB3(MOSI/OC2)_15") (pintype "bidirectional"))
    )
    (net (code "46") (name "Net-(BUT1B-C)") (class "Default")
      (node (ref "BUT1") (pin "K") (pinfunction "C_K") (pintype "passive"))
      (node (ref "R32") (pin "1") (pinfunction "1_1") (pintype "passive"))
    )
    (net (code "47") (name "Net-(BUTB-C)") (class "Default")
      (node (ref "BUT") (pin "K") (pinfunction "C_K") (pintype "passive"))
      (node (ref "R15") (pin "1") (pinfunction "1_1") (pintype "passive"))
    )
    (net (code "48") (name "Net-(C5-Pad-)") (class "Default")
      (node (ref "C5") (pin "-") (pinfunction "-_-") (pintype "passive"))
      (node (ref "D2") (pin "A") (pinfunction "A_A") (pintype "passive"))
    )
    (net (code "49") (name "Net-(D1-PadA)") (class "Default")
      (node (ref "D1") (pin "A") (pinfunction "A_A") (pintype "passive"))
      (node (ref "POWER") (pin "10") (pinfunction "10_10") (pintype "passive"))
      (node (ref "POWER") (pin "9") (pinfunction "9_9") (pintype "passive"))
    )
    (net (code "50") (name "Net-(D2-PadC)") (class "Default")
      (node (ref "D2") (pin "C") (pinfunction "C_C") (pintype "passive"))
      (node (ref "POWER") (pin "1") (pinfunction "1_1") (pintype "passive"))
      (node (ref "POWER") (pin "2") (pinfunction "2_2") (pintype "passive"))
    )
    (net (code "51") (name "Net-(D3-PadA)") (class "Default")
      (node (ref "D3") (pin "A") (pinfunction "A_A") (pintype "passive"))
      (node (ref "R16") (pin "2") (pinfunction "2_2") (pintype "passive"))
      (node (ref "R18") (pin "2") (pinfunction "2_2") (pintype "passive"))
    )
    (net (code "52") (name "Net-(D3-PadC)") (class "Default")
      (node (ref "D3") (pin "C") (pinfunction "C_C") (pintype "passive"))
      (node (ref "TRIGOUT") (pin "TIP") (pinfunction "TIP_TIP") (pintype "passive"))
    )
    (net (code "53") (name "Net-(D4-PadA)") (class "Default")
      (node (ref "D4") (pin "A") (pinfunction "A_A") (pintype "passive"))
      (node (ref "R30") (pin "2") (pinfunction "2_2") (pintype "passive"))
      (node (ref "R34") (pin "2") (pinfunction "2_2") (pintype "passive"))
    )
    (net (code "54") (name "Net-(D4-PadC)") (class "Default")
      (node (ref "D4") (pin "C") (pinfunction "C_C") (pintype "passive"))
      (node (ref "TRIGOUT2") (pin "TIP") (pinfunction "TIP_TIP") (pintype "passive"))
    )
    (net (code "55") (name "Net-(ENC1-Pad+G)") (class "Default")
      (node (ref "ENC1") (pin "+G") (pinfunction "+G_+G") (pintype "passive"))
      (node (ref "R27") (pin "1") (pinfunction "1_1") (pintype "passive"))
    )
    (net (code "56") (name "Net-(ENC1-Pad+R)") (class "Default")
      (node (ref "ENC1") (pin "+R") (pinfunction "+R_+R") (pintype "passive"))
      (node (ref "R21") (pin "1") (pinfunction "1_1") (pintype "passive"))
    )
    (net (code "57") (name "Net-(ENC1-PadA)") (class "Default")
      (node (ref "ENC1") (pin "A") (pinfunction "A_A") (pintype "bidirectional"))
      (node (ref "R2") (pin "1") (pinfunction "1_1") (pintype "passive"))
      (node (ref "R3") (pin "1") (pinfunction "1_1") (pintype "passive"))
    )
    (net (code "58") (name "Net-(ENC1-PadB)") (class "Default")
      (node (ref "ENC1") (pin "B") (pinfunction "B_B") (pintype "bidirectional"))
      (node (ref "R1") (pin "1") (pinfunction "1_1") (pintype "passive"))
      (node (ref "R4") (pin "1") (pinfunction "1_1") (pintype "passive"))
    )
    (net (code "59") (name "Net-(ENC2-Pad+G)") (class "Default")
      (node (ref "ENC2") (pin "+G") (pinfunction "+G_+G") (pintype "passive"))
      (node (ref "R38") (pin "1") (pinfunction "1_1") (pintype "passive"))
    )
    (net (code "60") (name "Net-(ENC2-Pad+R)") (class "Default")
      (node (ref "ENC2") (pin "+R") (pinfunction "+R_+R") (pintype "passive"))
      (node (ref "R31") (pin "1") (pinfunction "1_1") (pintype "passive"))
    )
    (net (code "61") (name "Net-(ENC2-PadA)") (class "Default")
      (node (ref "ENC2") (pin "A") (pinfunction "A_A") (pintype "bidirectional"))
      (node (ref "R10") (pin "1") (pinfunction "1_1") (pintype "passive"))
      (node (ref "R11") (pin "1") (pinfunction "1_1") (pintype "passive"))
    )
    (net (code "62") (name "Net-(ENC2-PadB)") (class "Default")
      (node (ref "ENC2") (pin "B") (pinfunction "B_B") (pintype "bidirectional"))
      (node (ref "R12") (pin "1") (pinfunction "1_1") (pintype "passive"))
      (node (ref "R6") (pin "1") (pinfunction "1_1") (pintype "passive"))
    )
    (net (code "63") (name "Net-(IC3A-+IN)") (class "Default")
      (node (ref "C6") (pin "1") (pinfunction "1_1") (pintype "passive"))
      (node (ref "IC3") (pin "3") (pinfunction "+IN_3") (pintype "input"))
      (node (ref "R16") (pin "1") (pinfunction "1_1") (pintype "passive"))
      (node (ref "R17") (pin "2") (pinfunction "2_2") (pintype "passive"))
    )
    (net (code "64") (name "Net-(IC3A-OUT)") (class "Default")
      (node (ref "C6") (pin "2") (pinfunction "2_2") (pintype "passive"))
      (node (ref "IC3") (pin "1") (pinfunction "OUT_1") (pintype "output"))
      (node (ref "R18") (pin "1") (pinfunction "1_1") (pintype "passive"))
    )
    (net (code "65") (name "Net-(IC3B-+IN)") (class "Default")
      (node (ref "C14") (pin "1") (pinfunction "1_1") (pintype "passive"))
      (node (ref "IC3") (pin "5") (pinfunction "+IN_5") (pintype "input"))
      (node (ref "R34") (pin "1") (pinfunction "1_1") (pintype "passive"))
      (node (ref "R35") (pin "2") (pinfunction "2_2") (pintype "passive"))
    )
    (net (code "66") (name "Net-(IC3B-OUT)") (class "Default")
      (node (ref "C14") (pin "2") (pinfunction "2_2") (pintype "passive"))
      (node (ref "IC3") (pin "7") (pinfunction "OUT_7") (pintype "output"))
      (node (ref "R30") (pin "1") (pinfunction "1_1") (pintype "passive"))
    )
    (net (code "67") (name "Net-(Q3-PadC)") (class "Default")
      (node (ref "Q3") (pin "C") (pinfunction "C_C") (pintype "passive"))
      (node (ref "R23") (pin "2") (pinfunction "2_2") (pintype "passive"))
    )
    (net (code "68") (name "Net-(Q4-PadC)") (class "Default")
      (node (ref "Q4") (pin "C") (pinfunction "C_C") (pintype "passive"))
      (node (ref "R22") (pin "2") (pinfunction "2_2") (pintype "passive"))
    )
    (net (code "69") (name "Net-(Q5-PadC)") (class "Default")
      (node (ref "Q5") (pin "C") (pinfunction "C_C") (pintype "passive"))
      (node (ref "R29") (pin "2") (pinfunction "2_2") (pintype "passive"))
    )
    (net (code "70") (name "Net-(Q6-PadC)") (class "Default")
      (node (ref "Q6") (pin "C") (pinfunction "C_C") (pintype "passive"))
      (node (ref "R25") (pin "2") (pinfunction "2_2") (pintype "passive"))
    )
    (net (code "71") (name "Net-(Q7-PadC)") (class "Default")
      (node (ref "Q7") (pin "C") (pinfunction "C_C") (pintype "passive"))
      (node (ref "R28") (pin "2") (pinfunction "2_2") (pintype "passive"))
    )
    (net (code "72") (name "Net-(Q8-PadC)") (class "Default")
      (node (ref "Q8") (pin "C") (pinfunction "C_C") (pintype "passive"))
      (node (ref "R26") (pin "2") (pinfunction "2_2") (pintype "passive"))
    )
    (net (code "73") (name "Net-(Q9-PadC)") (class "Default")
      (node (ref "Q9") (pin "C") (pinfunction "C_C") (pintype "passive"))
      (node (ref "R24") (pin "2") (pinfunction "2_2") (pintype "passive"))
    )
    (net (code "74") (name "Net-(R8-Pad2)") (class "Default")
      (node (ref "R8") (pin "2") (pinfunction "2_2") (pintype "passive"))
      (node (ref "TRIGATEIN") (pin "TIP") (pinfunction "TIP_TIP") (pintype "passive"))
    )
    (net (code "75") (name "Net-(R13-Pad2)") (class "Default")
      (node (ref "R13") (pin "2") (pinfunction "2_2") (pintype "passive"))
      (node (ref "R8") (pin "1") (pinfunction "1_1") (pintype "passive"))
      (node (ref "T1") (pin "B") (pinfunction "B_B") (pintype "passive"))
    )
    (net (code "76") (name "Net-(U1-PB6(XTAL1{slash}TOSC1))") (class "Default")
      (node (ref "C1") (pin "1") (pinfunction "1_1") (pintype "passive"))
      (node (ref "Q1") (pin "2") (pinfunction "2_2") (pintype "passive"))
      (node (ref "U1") (pin "7") (pinfunction "PB6(XTAL1/TOSC1)_7") (pintype "bidirectional"))
    )
    (net (code "77") (name "Net-(U1-PB7(XTAL2{slash}TOSC2))") (class "Default")
      (node (ref "C2") (pin "1") (pinfunction "1_1") (pintype "passive"))
      (node (ref "Q1") (pin "1") (pinfunction "1_1") (pintype "passive"))
      (node (ref "U1") (pin "8") (pinfunction "PB7(XTAL2/TOSC2)_8") (pintype "bidirectional"))
    )
    (net (code "78") (name "Net-(U4-PB6(XTAL1{slash}TOSC1))") (class "Default")
      (node (ref "C3") (pin "1") (pinfunction "1_1") (pintype "passive"))
      (node (ref "Q2") (pin "2") (pinfunction "2_2") (pintype "passive"))
      (node (ref "U4") (pin "7") (pinfunction "PB6(XTAL1/TOSC1)_7") (pintype "bidirectional"))
    )
    (net (code "79") (name "Net-(U4-PB7(XTAL2{slash}TOSC2))") (class "Default")
      (node (ref "C13") (pin "1") (pinfunction "1_1") (pintype "passive"))
      (node (ref "Q2") (pin "1") (pinfunction "1_1") (pintype "passive"))
      (node (ref "U4") (pin "8") (pinfunction "PB7(XTAL2/TOSC2)_8") (pintype "bidirectional"))
    )
    (net (code "80") (name "RST") (class "Default")
      (node (ref "ISP1") (pin "5") (pinfunction "RST_5") (pintype "output"))
      (node (ref "U1") (pin "29") (pinfunction "PC6(/RESET)_29") (pintype "bidirectional"))
    )
    (net (code "81") (name "RST2") (class "Default")
      (node (ref "ISP2") (pin "5") (pinfunction "RST_5") (pintype "output"))
      (node (ref "U4") (pin "29") (pinfunction "PC6(/RESET)_29") (pintype "bidirectional"))
    )
    (net (code "82") (name "SCK") (class "Default")
      (node (ref "ISP1") (pin "3") (pinfunction "SCK_3") (pintype "output"))
      (node (ref "U1") (pin "17") (pinfunction "PB5(SCK)_17") (pintype "bidirectional"))
    )
    (net (code "83") (name "SCK2") (class "Default")
      (node (ref "ISP2") (pin "3") (pinfunction "SCK_3") (pintype "output"))
      (node (ref "U4") (pin "17") (pinfunction "PB5(SCK)_17") (pintype "bidirectional"))
    )
    (net (code "84") (name "SCL") (class "Default")
      (node (ref "R37") (pin "2") (pinfunction "2_2") (pintype "passive"))
      (node (ref "U1") (pin "28") (pinfunction "PC5(ADC5/SCL)_28") (pintype "bidirectional"))
      (node (ref "U4") (pin "28") (pinfunction "PC5(ADC5/SCL)_28") (pintype "bidirectional"))
    )
    (net (code "85") (name "SDA") (class "Default")
      (node (ref "R36") (pin "2") (pinfunction "2_2") (pintype "passive"))
      (node (ref "U1") (pin "27") (pinfunction "PC4(ADC4/SDA)_27") (pintype "bidirectional"))
      (node (ref "U4") (pin "27") (pinfunction "PC4(ADC4/SDA)_27") (pintype "bidirectional"))
    )
    (net (code "86") (name "TRIG1") (class "Default")
      (node (ref "BUT1") (pin "A") (pinfunction "A_A") (pintype "passive"))
      (node (ref "IC3") (pin "6") (pinfunction "-IN_6") (pintype "input"))
      (node (ref "R33") (pin "2") (pinfunction "2_2") (pintype "passive"))
      (node (ref "U1") (pin "13") (pinfunction "PB1(OC1A)_13") (pintype "bidirectional"))
    )
    (net (code "87") (name "TRIGO") (class "Default")
      (node (ref "BUT") (pin "A") (pinfunction "A_A") (pintype "passive"))
      (node (ref "IC3") (pin "2") (pinfunction "-IN_2") (pintype "input"))
      (node (ref "R19") (pin "2") (pinfunction "2_2") (pintype "passive"))
      (node (ref "U1") (pin "12") (pinfunction "PB0(ICP)_12") (pintype "bidirectional"))
    )
    (net (code "88") (name "unconnected-(DS1-ANODE_DP-Pad7)") (class "Default")
      (node (ref "DS1") (pin "7") (pinfunction "ANODE_DP_7") (pintype "input"))
    )
    (net (code "89") (name "unconnected-(DS1-ANODE_L1_L2-Pad12)") (class "Default")
      (node (ref "DS1") (pin "12") (pinfunction "ANODE_L1_L2_12") (pintype "input"))
    )
    (net (code "90") (name "unconnected-(DS1-ANODE_L3-Pad9)") (class "Default")
      (node (ref "DS1") (pin "9") (pinfunction "ANODE_L3_9") (pintype "input"))
    )
    (net (code "91") (name "unconnected-(DS1-CATHODE_L3-Pad10)") (class "Default")
      (node (ref "DS1") (pin "10") (pinfunction "CATHODE_L3_10") (pintype "input"))
    )
    (net (code "92") (name "unconnected-(DS1-COMMON_CATHODE_L1_L2-Pad4)") (class "Default")
      (node (ref "DS1") (pin "4") (pinfunction "COMMON_CATHODE_L1_L2_4") (pintype "input"))
    )
    (net (code "93") (name "unconnected-(TRIGATEIN-PadNORM)") (class "Default")
      (node (ref "TRIGATEIN") (pin "NORM") (pinfunction "NORM_NORM") (pintype "passive"))
    )
    (net (code "94") (name "unconnected-(TRIGOUT-PadNORM)") (class "Default")
      (node (ref "TRIGOUT") (pin "NORM") (pinfunction "NORM_NORM") (pintype "passive"))
    )
    (net (code "95") (name "unconnected-(TRIGOUT2-PadNORM)") (class "Default")
      (node (ref "TRIGOUT2") (pin "NORM") (pinfunction "NORM_NORM") (pintype "passive"))
    )
    (net (code "96") (name "unconnected-(U1-AGND-Pad21)") (class "Default")
      (node (ref "U1") (pin "21") (pinfunction "AGND_21") (pintype "bidirectional"))
    )
    (net (code "97") (name "unconnected-(U1-PB2(SS{slash}OC1B)-Pad14)") (class "Default")
      (node (ref "U1") (pin "14") (pinfunction "PB2(SS/OC1B)_14") (pintype "bidirectional"))
    )
    (net (code "98") (name "unconnected-(U1-PD1(TXD)-Pad31)") (class "Default")
      (node (ref "U1") (pin "31") (pinfunction "PD1(TXD)_31") (pintype "bidirectional"))
    )
    (net (code "99") (name "unconnected-(U1-VCC-Pad6)") (class "Default")
      (node (ref "U1") (pin "6") (pinfunction "VCC_6") (pintype "bidirectional"))
    )
    (net (code "100") (name "unconnected-(U4-ADC6-Pad19)") (class "Default")
      (node (ref "U4") (pin "19") (pinfunction "ADC6_19") (pintype "bidirectional"))
    )
    (net (code "101") (name "unconnected-(U4-ADC7-Pad22)") (class "Default")
      (node (ref "U4") (pin "22") (pinfunction "ADC7_22") (pintype "bidirectional"))
    )
    (net (code "102") (name "unconnected-(U4-PD0(RXD)-Pad30)") (class "Default")
      (node (ref "U4") (pin "30") (pinfunction "PD0(RXD)_30") (pintype "bidirectional"))
    )
    (net (code "103") (name "unconnected-(U4-PD1(TXD)-Pad31)") (class "Default")
      (node (ref "U4") (pin "31") (pinfunction "PD1(TXD)_31") (pintype "bidirectional"))
    )
    (net (code "104") (name "unconnected-(U4-VCC-Pad6)") (class "Default")
      (node (ref "U4") (pin "6") (pinfunction "VCC_6") (pintype "bidirectional"))
    )
  )
)
